# AHD_Ethernet.net
KiCad netlist of a schematic drawn in Altium Designer
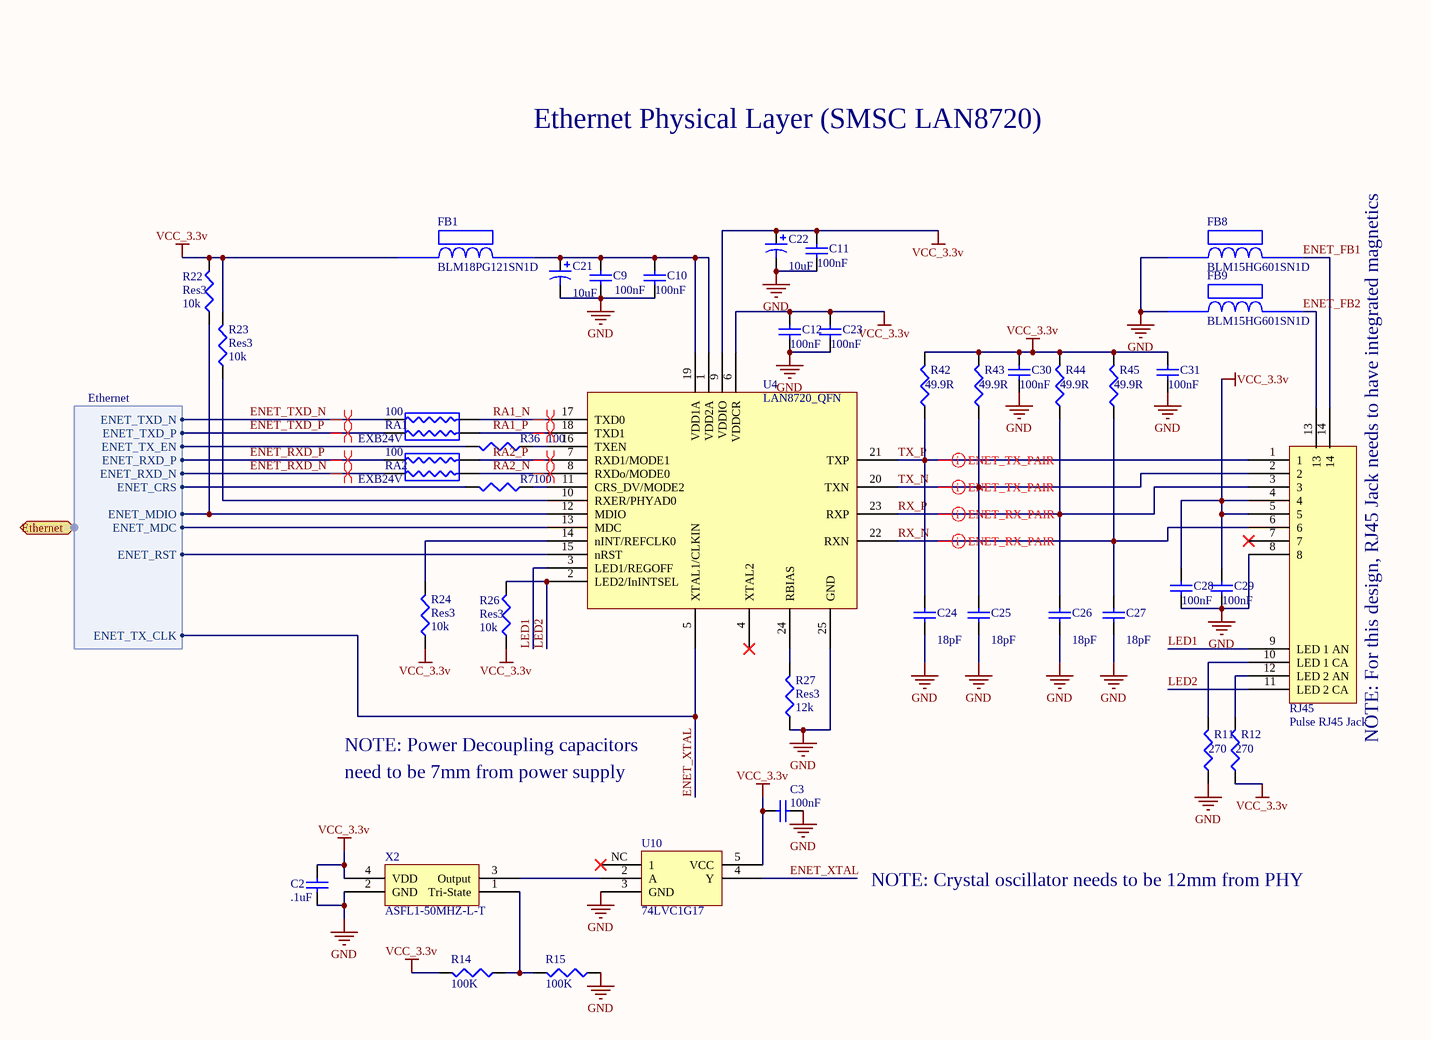
[diagram p0: AHD Ethernet.SchDoc]

(export (version "E")
  (design (tool "Eeschema 10.0.6"))
  (components
    (comp (ref "C2")
      (value ".1uF")
      (footprint "1608[0603]")
      (description "Capacitor (Semiconductor SIM Model)")
      (fields (field (name "Comment") "Cap Semi") (field (name "PUBLISHER") "Altium Limited"))
      (libsource (lib "Miscellaneous Devices") (part "Cap Semi"))
    )
    (comp (ref "C3")
      (value "100nF")
      (footprint "1608[0603]")
      (description "Capacitor (Semiconductor SIM Model)")
      (fields (field (name "Comment") "Cap Semi") (field (name "PUBLISHER") "Altium Limited"))
      (libsource (lib "Miscellaneous Devices") (part "Cap Semi"))
    )
    (comp (ref "C9")
      (value "100nF")
      (footprint "1608[0603]")
      (description "Capacitor (Semiconductor SIM Model)")
      (fields (field (name "Comment") "Cap Semi") (field (name "PUBLISHER") "Altium Limited"))
      (libsource (lib "Miscellaneous Devices") (part "Cap Semi"))
    )
    (comp (ref "C10")
      (value "100nF")
      (footprint "1608[0603]")
      (description "Capacitor (Semiconductor SIM Model)")
      (fields (field (name "Comment") "Cap Semi") (field (name "PUBLISHER") "Altium Limited"))
      (libsource (lib "Miscellaneous Devices") (part "Cap Semi"))
    )
    (comp (ref "C11")
      (value "100nF")
      (footprint "1608[0603]")
      (description "Capacitor (Semiconductor SIM Model)")
      (fields (field (name "Comment") "Cap Semi") (field (name "PUBLISHER") "Altium Limited"))
      (libsource (lib "Miscellaneous Devices") (part "Cap Semi"))
    )
    (comp (ref "C12")
      (value "100nF")
      (footprint "1608[0603]")
      (description "Capacitor (Semiconductor SIM Model)")
      (fields (field (name "Comment") "Cap Semi") (field (name "PUBLISHER") "Altium Limited"))
      (libsource (lib "Miscellaneous Devices") (part "Cap Semi"))
    )
    (comp (ref "C21")
      (value "10uF")
      (footprint "CAPC1608L")
      (description "Polarized Capacitor (Surface Mount)")
      (fields (field (name "Comment") "Cap Pol3") (field (name "PUBLISHER") "Altium Limited"))
      (libsource (lib "Miscellaneous Devices") (part "Cap Pol3"))
    )
    (comp (ref "C22")
      (value "10uF")
      (footprint "CAPC1608L")
      (description "Polarized Capacitor (Surface Mount)")
      (fields (field (name "Comment") "Cap Pol3") (field (name "PUBLISHER") "Altium Limited"))
      (libsource (lib "Miscellaneous Devices") (part "Cap Pol3"))
    )
    (comp (ref "C23")
      (value "100nF")
      (footprint "1608[0603]")
      (description "Capacitor (Semiconductor SIM Model)")
      (fields (field (name "Comment") "Cap Semi") (field (name "PUBLISHER") "Altium Limited"))
      (libsource (lib "Miscellaneous Devices") (part "Cap Semi"))
    )
    (comp (ref "C24")
      (value "18pF")
      (footprint "1608[0603]")
      (description "Capacitor (Semiconductor SIM Model)")
      (fields (field (name "Comment") "Cap Semi") (field (name "PUBLISHER") "Altium Limited"))
      (libsource (lib "Miscellaneous Devices") (part "Cap Semi"))
    )
    (comp (ref "C25")
      (value "18pF")
      (footprint "1608[0603]")
      (description "Capacitor (Semiconductor SIM Model)")
      (fields (field (name "Comment") "Cap Semi") (field (name "PUBLISHER") "Altium Limited"))
      (libsource (lib "Miscellaneous Devices") (part "Cap Semi"))
    )
    (comp (ref "C26")
      (value "18pF")
      (footprint "1608[0603]")
      (description "Capacitor (Semiconductor SIM Model)")
      (fields (field (name "Comment") "Cap Semi") (field (name "PUBLISHER") "Altium Limited"))
      (libsource (lib "Miscellaneous Devices") (part "Cap Semi"))
    )
    (comp (ref "C27")
      (value "18pF")
      (footprint "1608[0603]")
      (description "Capacitor (Semiconductor SIM Model)")
      (fields (field (name "Comment") "Cap Semi") (field (name "PUBLISHER") "Altium Limited"))
      (libsource (lib "Miscellaneous Devices") (part "Cap Semi"))
    )
    (comp (ref "C28")
      (value "100nF")
      (footprint "1608[0603]")
      (description "Capacitor (Semiconductor SIM Model)")
      (fields (field (name "Comment") "Cap Semi") (field (name "PUBLISHER") "Altium Limited"))
      (libsource (lib "Miscellaneous Devices") (part "Cap Semi"))
    )
    (comp (ref "C29")
      (value "100nF")
      (footprint "1608[0603]")
      (description "Capacitor (Semiconductor SIM Model)")
      (fields (field (name "Comment") "Cap Semi") (field (name "PUBLISHER") "Altium Limited"))
      (libsource (lib "Miscellaneous Devices") (part "Cap Semi"))
    )
    (comp (ref "C30")
      (value "100nF")
      (footprint "1608[0603]")
      (description "Capacitor (Semiconductor SIM Model)")
      (fields (field (name "Comment") "Cap Semi") (field (name "PUBLISHER") "Altium Limited"))
      (libsource (lib "Miscellaneous Devices") (part "Cap Semi"))
    )
    (comp (ref "C31")
      (value "100nF")
      (footprint "1608[0603]")
      (description "Capacitor (Semiconductor SIM Model)")
      (fields (field (name "Comment") "Cap Semi") (field (name "PUBLISHER") "Altium Limited"))
      (libsource (lib "Miscellaneous Devices") (part "Cap Semi"))
    )
    (comp (ref "FB1")
      (value "BLM18PG121SN1D")
      (footprint "BLM18PG121SN1D")
      (libsource (lib "AHD Part Library") (part "BLM18PG121SN1D"))
    )
    (comp (ref "FB8")
      (value "BLM15HG601SN1D")
      (footprint "BLM18PG121SN1D")
      (libsource (lib "AHD Part Library") (part "BLM15HG601SN1D"))
    )
    (comp (ref "FB9")
      (value "BLM15HG601SN1D")
      (footprint "BLM18PG121SN1D")
      (libsource (lib "AHD Part Library") (part "BLM15HG601SN1D"))
    )
    (comp (ref "R7")
      (value "100")
      (footprint "J1-0603")
      (description "Resistor")
      (fields (field (name "Comment") "Res3") (field (name "PUBLISHER") "Altium Limited"))
      (libsource (lib "Miscellaneous Devices") (part "Res3"))
    )
    (comp (ref "R11")
      (value "270")
      (footprint "J1-0603")
      (description "Resistor")
      (fields (field (name "Comment") "Res3") (field (name "PUBLISHER") "Altium Limited"))
      (libsource (lib "Miscellaneous Devices") (part "Res3"))
    )
    (comp (ref "R12")
      (value "270")
      (footprint "J1-0603")
      (description "Resistor")
      (fields (field (name "Comment") "Res3") (field (name "PUBLISHER") "Altium Limited"))
      (libsource (lib "Miscellaneous Devices") (part "Res3"))
    )
    (comp (ref "R14")
      (value "100K")
      (footprint "J1-0603")
      (description "Resistor")
      (fields (field (name "Comment") "Res3") (field (name "PUBLISHER") "Altium Limited"))
      (libsource (lib "Miscellaneous Devices") (part "Res3"))
    )
    (comp (ref "R15")
      (value "100K")
      (footprint "J1-0603")
      (description "Resistor")
      (fields (field (name "Comment") "Res3") (field (name "PUBLISHER") "Altium Limited"))
      (libsource (lib "Miscellaneous Devices") (part "Res3"))
    )
    (comp (ref "R22")
      (value "Res3")
      (footprint "J1-0603")
      (description "Resistor")
      (fields (field (name "ALTIUM_VALUE") "10k") (field (name "PUBLISHER") "Altium Limited"))
      (libsource (lib "Miscellaneous Devices") (part "Res3"))
    )
    (comp (ref "R23")
      (value "Res3")
      (footprint "J1-0603")
      (description "Resistor")
      (fields (field (name "ALTIUM_VALUE") "10k") (field (name "PUBLISHER") "Altium Limited"))
      (libsource (lib "Miscellaneous Devices") (part "Res3"))
    )
    (comp (ref "R24")
      (value "Res3")
      (footprint "J1-0603")
      (description "Resistor")
      (fields (field (name "ALTIUM_VALUE") "10k") (field (name "PUBLISHER") "Altium Limited"))
      (libsource (lib "Miscellaneous Devices") (part "Res3"))
    )
    (comp (ref "R26")
      (value "Res3")
      (footprint "J1-0603")
      (description "Resistor")
      (fields (field (name "ALTIUM_VALUE") "10k") (field (name "PUBLISHER") "Altium Limited"))
      (libsource (lib "Miscellaneous Devices") (part "Res3"))
    )
    (comp (ref "R27")
      (value "Res3")
      (footprint "J1-0603")
      (description "Resistor")
      (fields (field (name "ALTIUM_VALUE") "12k") (field (name "PUBLISHER") "Altium Limited"))
      (libsource (lib "Miscellaneous Devices") (part "Res3"))
    )
    (comp (ref "R36")
      (value "100")
      (footprint "J1-0603")
      (description "Resistor")
      (fields (field (name "Comment") "Res3") (field (name "PUBLISHER") "Altium Limited"))
      (libsource (lib "Miscellaneous Devices") (part "Res3"))
    )
    (comp (ref "R42")
      (value "49.9R")
      (footprint "J1-0603")
      (description "Resistor")
      (fields (field (name "Comment") "Res3") (field (name "PUBLISHER") "Altium Limited"))
      (libsource (lib "Miscellaneous Devices") (part "Res3"))
    )
    (comp (ref "R43")
      (value "49.9R")
      (footprint "J1-0603")
      (description "Resistor")
      (fields (field (name "Comment") "Res3") (field (name "PUBLISHER") "Altium Limited"))
      (libsource (lib "Miscellaneous Devices") (part "Res3"))
    )
    (comp (ref "R44")
      (value "49.9R")
      (footprint "J1-0603")
      (description "Resistor")
      (fields (field (name "Comment") "Res3") (field (name "PUBLISHER") "Altium Limited"))
      (libsource (lib "Miscellaneous Devices") (part "Res3"))
    )
    (comp (ref "R45")
      (value "49.9R")
      (footprint "J1-0603")
      (description "Resistor")
      (fields (field (name "Comment") "Res3") (field (name "PUBLISHER") "Altium Limited"))
      (libsource (lib "Miscellaneous Devices") (part "Res3"))
    )
    (comp (ref "RA1")
      (value "EXB24V")
      (footprint "EXB24V - Res Array x2")
      (fields (field (name "ALTIUM_VALUE") "100"))
      (libsource (lib "AHD Part Library") (part "EXB24V - Res Array x2"))
    )
    (comp (ref "RA2")
      (value "EXB24V")
      (footprint "EXB24V - Res Array x2")
      (fields (field (name "ALTIUM_VALUE") "100"))
      (libsource (lib "AHD Part Library") (part "EXB24V - Res Array x2"))
    )
    (comp (ref "RJ45")
      (value "Pulse RJ45 Jack")
      (footprint "J0006D21BNL")
      (libsource (lib "AHD Part Library") (part "Pulse RJ45_ICM_LED_Jack"))
    )
    (comp (ref "U4")
      (value "LAN8720_QFN")
      (footprint "LAN8720_QFN")
      (libsource (lib "AHD Part Library") (part "LAN8720 QFN"))
    )
    (comp (ref "U10")
      (value "74LVC1G17")
      (footprint "74LVC1G17")
      (libsource (lib "AHD Part Library") (part "74LVC1G17"))
    )
    (comp (ref "X2")
      (value "ASFL1-50MHZ-L-T")
      (footprint "ASFL1-50MHZ-L-T")
      (libsource (lib "AHD Part Library") (part "ASFL1-50MHZ-L-T"))
    )
  )
  (nets
    (net (code "2") (name "/ENET_CRS") (class "Default")
      (node (ref "R7") (pin "2") (pinfunction "2_2") (pintype "passive"))
    )
    (net (code "3") (name "/ENET_FB1") (class "Default")
      (node (ref "FB8") (pin "2") (pinfunction "2_2") (pintype "passive"))
      (node (ref "RJ45") (pin "14") (pinfunction "14_14") (pintype "passive"))
    )
    (net (code "4") (name "/ENET_FB2") (class "Default")
      (node (ref "FB9") (pin "2") (pinfunction "2_2") (pintype "passive"))
      (node (ref "RJ45") (pin "13") (pinfunction "13_13") (pintype "passive"))
    )
    (net (code "5") (name "/ENET_MDC") (class "Default")
      (node (ref "U4") (pin "13") (pinfunction "MDC_13") (pintype "passive"))
    )
    (net (code "6") (name "/ENET_MDIO") (class "Default")
      (node (ref "R22") (pin "1") (pinfunction "1_1") (pintype "passive"))
      (node (ref "U4") (pin "12") (pinfunction "MDIO_12") (pintype "passive"))
    )
    (net (code "7") (name "/ENET_RST") (class "Default")
      (node (ref "U4") (pin "15") (pinfunction "nRST_15") (pintype "passive"))
    )
    (net (code "8") (name "/ENET_RXD_N") (class "Default")
      (node (ref "RA2") (pin "1") (pinfunction "1_1") (pintype "passive"))
    )
    (net (code "9") (name "/ENET_RXD_P") (class "Default")
      (node (ref "RA2") (pin "3") (pinfunction "3_3") (pintype "passive"))
    )
    (net (code "10") (name "/ENET_TXD_N") (class "Default")
      (node (ref "RA1") (pin "3") (pinfunction "3_3") (pintype "passive"))
    )
    (net (code "11") (name "/ENET_TXD_P") (class "Default")
      (node (ref "RA1") (pin "1") (pinfunction "1_1") (pintype "passive"))
    )
    (net (code "12") (name "/ENET_TX_EN") (class "Default")
      (node (ref "R36") (pin "2") (pinfunction "2_2") (pintype "passive"))
    )
    (net (code "13") (name "/ENET_XTAL") (class "Default")
      (node (ref "U10") (pin "4") (pinfunction "Y_4") (pintype "passive"))
      (node (ref "U4") (pin "5") (pinfunction "XTAL1/CLKIN_5") (pintype "passive"))
    )
    (net (code "14") (name "/LED1") (class "Default")
      (node (ref "RJ45") (pin "9") (pinfunction "LED_1_AN_9") (pintype "passive"))
      (node (ref "U4") (pin "3") (pinfunction "LED1/REGOFF_3") (pintype "passive"))
    )
    (net (code "15") (name "/LED2") (class "Default")
      (node (ref "R26") (pin "2") (pinfunction "2_2") (pintype "passive"))
      (node (ref "RJ45") (pin "11") (pinfunction "LED_2_CA_11") (pintype "passive"))
      (node (ref "U4") (pin "2") (pinfunction "LED2/InINTSEL_2") (pintype "passive"))
    )
    (net (code "16") (name "/RA1_N") (class "Default")
      (node (ref "RA1") (pin "4") (pinfunction "4_4") (pintype "passive"))
      (node (ref "U4") (pin "17") (pinfunction "TXD0_17") (pintype "passive"))
    )
    (net (code "17") (name "/RA1_P") (class "Default")
      (node (ref "RA1") (pin "2") (pinfunction "2_2") (pintype "passive"))
      (node (ref "U4") (pin "18") (pinfunction "TXD1_18") (pintype "passive"))
    )
    (net (code "18") (name "/RA2_N") (class "Default")
      (node (ref "RA2") (pin "2") (pinfunction "2_2") (pintype "passive"))
      (node (ref "U4") (pin "8") (pinfunction "RXDo/MODE0_8") (pintype "passive"))
    )
    (net (code "19") (name "/RA2_P") (class "Default")
      (node (ref "RA2") (pin "4") (pinfunction "4_4") (pintype "passive"))
      (node (ref "U4") (pin "7") (pinfunction "RXD1/MODE1_7") (pintype "passive"))
    )
    (net (code "20") (name "/RX_N") (class "Default")
      (node (ref "C27") (pin "2") (pinfunction "2_2") (pintype "passive"))
      (node (ref "R45") (pin "1") (pinfunction "1_1") (pintype "passive"))
      (node (ref "RJ45") (pin "6") (pinfunction "6_6") (pintype "passive"))
      (node (ref "U4") (pin "22") (pinfunction "RXN_22") (pintype "passive"))
    )
    (net (code "21") (name "/RX_P") (class "Default")
      (node (ref "C26") (pin "2") (pinfunction "2_2") (pintype "passive"))
      (node (ref "R44") (pin "1") (pinfunction "1_1") (pintype "passive"))
      (node (ref "RJ45") (pin "3") (pinfunction "3_3") (pintype "passive"))
      (node (ref "U4") (pin "23") (pinfunction "RXP_23") (pintype "passive"))
    )
    (net (code "22") (name "/TX_N") (class "Default")
      (node (ref "C25") (pin "2") (pinfunction "2_2") (pintype "passive"))
      (node (ref "R43") (pin "1") (pinfunction "1_1") (pintype "passive"))
      (node (ref "RJ45") (pin "2") (pinfunction "2_2") (pintype "passive"))
      (node (ref "U4") (pin "20") (pinfunction "TXN_20") (pintype "passive"))
    )
    (net (code "23") (name "/TX_P") (class "Default")
      (node (ref "C24") (pin "2") (pinfunction "2_2") (pintype "passive"))
      (node (ref "R42") (pin "1") (pinfunction "1_1") (pintype "passive"))
      (node (ref "RJ45") (pin "1") (pinfunction "1_1") (pintype "passive"))
      (node (ref "U4") (pin "21") (pinfunction "TXP_21") (pintype "passive"))
    )
    (net (code "25") (name "GND") (class "Default")
      (node (ref "C10") (pin "1") (pinfunction "1_1") (pintype "passive"))
      (node (ref "C11") (pin "1") (pinfunction "1_1") (pintype "passive"))
      (node (ref "C12") (pin "1") (pinfunction "1_1") (pintype "passive"))
      (node (ref "C2") (pin "1") (pinfunction "1_1") (pintype "passive"))
      (node (ref "C21") (pin "2") (pinfunction "2_2") (pintype "passive"))
      (node (ref "C22") (pin "2") (pinfunction "2_2") (pintype "passive"))
      (node (ref "C23") (pin "1") (pinfunction "1_1") (pintype "passive"))
      (node (ref "C24") (pin "1") (pinfunction "1_1") (pintype "passive"))
      (node (ref "C25") (pin "1") (pinfunction "1_1") (pintype "passive"))
      (node (ref "C26") (pin "1") (pinfunction "1_1") (pintype "passive"))
      (node (ref "C27") (pin "1") (pinfunction "1_1") (pintype "passive"))
      (node (ref "C28") (pin "1") (pinfunction "1_1") (pintype "passive"))
      (node (ref "C29") (pin "1") (pinfunction "1_1") (pintype "passive"))
      (node (ref "C3") (pin "1") (pinfunction "1_1") (pintype "passive"))
      (node (ref "C30") (pin "1") (pinfunction "1_1") (pintype "passive"))
      (node (ref "C31") (pin "1") (pinfunction "1_1") (pintype "passive"))
      (node (ref "C9") (pin "1") (pinfunction "1_1") (pintype "passive"))
      (node (ref "FB8") (pin "1") (pinfunction "1_1") (pintype "passive"))
      (node (ref "FB9") (pin "1") (pinfunction "1_1") (pintype "passive"))
      (node (ref "R11") (pin "1") (pinfunction "1_1") (pintype "passive"))
      (node (ref "R15") (pin "1") (pinfunction "1_1") (pintype "passive"))
      (node (ref "R27") (pin "1") (pinfunction "1_1") (pintype "passive"))
      (node (ref "RJ45") (pin "8") (pinfunction "8_8") (pintype "passive"))
      (node (ref "U10") (pin "3") (pinfunction "GND_3") (pintype "passive"))
      (node (ref "U4") (pin "25") (pinfunction "GND_25") (pintype "passive"))
      (node (ref "X2") (pin "2") (pinfunction "GND_2") (pintype "passive"))
    )
    (net (code "26") (name "Net-(RJ45-LED_1_CA)") (class "Default")
      (node (ref "R11") (pin "2") (pinfunction "2_2") (pintype "passive"))
      (node (ref "RJ45") (pin "10") (pinfunction "LED_1_CA_10") (pintype "passive"))
    )
    (net (code "27") (name "Net-(RJ45-LED_2_AN)") (class "Default")
      (node (ref "R12") (pin "2") (pinfunction "2_2") (pintype "passive"))
      (node (ref "RJ45") (pin "12") (pinfunction "LED_2_AN_12") (pintype "passive"))
    )
    (net (code "28") (name "Net-(U4-CRS_DV{slash}MODE2)") (class "Default")
      (node (ref "R7") (pin "1") (pinfunction "1_1") (pintype "passive"))
      (node (ref "U4") (pin "11") (pinfunction "CRS_DV/MODE2_11") (pintype "passive"))
    )
    (net (code "29") (name "Net-(U4-RBIAS)") (class "Default")
      (node (ref "R27") (pin "2") (pinfunction "2_2") (pintype "passive"))
      (node (ref "U4") (pin "24") (pinfunction "RBIAS_24") (pintype "passive"))
    )
    (net (code "30") (name "Net-(U4-RXER{slash}PHYAD0)") (class "Default")
      (node (ref "R23") (pin "1") (pinfunction "1_1") (pintype "passive"))
      (node (ref "U4") (pin "10") (pinfunction "RXER/PHYAD0_10") (pintype "passive"))
    )
    (net (code "31") (name "Net-(U4-TXEN)") (class "Default")
      (node (ref "R36") (pin "1") (pinfunction "1_1") (pintype "passive"))
      (node (ref "U4") (pin "16") (pinfunction "TXEN_16") (pintype "passive"))
    )
    (net (code "32") (name "Net-(U4-VDD1A)") (class "Default")
      (node (ref "C10") (pin "2") (pinfunction "2_2") (pintype "passive"))
      (node (ref "C21") (pin "1") (pinfunction "1_1") (pintype "passive"))
      (node (ref "C9") (pin "2") (pinfunction "2_2") (pintype "passive"))
      (node (ref "FB1") (pin "2") (pinfunction "2_2") (pintype "passive"))
      (node (ref "U4") (pin "1") (pinfunction "VDD2A_1") (pintype "passive"))
      (node (ref "U4") (pin "19") (pinfunction "VDD1A_19") (pintype "passive"))
    )
    (net (code "33") (name "Net-(U4-nINT{slash}REFCLK0)") (class "Default")
      (node (ref "R24") (pin "2") (pinfunction "2_2") (pintype "passive"))
      (node (ref "U4") (pin "14") (pinfunction "nINT/REFCLK0_14") (pintype "passive"))
    )
    (net (code "34") (name "Net-(U10-A)") (class "Default")
      (node (ref "U10") (pin "2") (pinfunction "A_2") (pintype "passive"))
      (node (ref "X2") (pin "3") (pinfunction "Output_3") (pintype "passive"))
    )
    (net (code "35") (name "Net-(X2-Tri-State)") (class "Default")
      (node (ref "R14") (pin "1") (pinfunction "1_1") (pintype "passive"))
      (node (ref "R15") (pin "2") (pinfunction "2_2") (pintype "passive"))
      (node (ref "X2") (pin "1") (pinfunction "Tri-State_1") (pintype "passive"))
    )
    (net (code "36") (name "VCC_3.3v") (class "Default")
      (node (ref "C11") (pin "2") (pinfunction "2_2") (pintype "passive"))
      (node (ref "C12") (pin "2") (pinfunction "2_2") (pintype "passive"))
      (node (ref "C2") (pin "2") (pinfunction "2_2") (pintype "passive"))
      (node (ref "C22") (pin "1") (pinfunction "1_1") (pintype "passive"))
      (node (ref "C23") (pin "2") (pinfunction "2_2") (pintype "passive"))
      (node (ref "C28") (pin "2") (pinfunction "2_2") (pintype "passive"))
      (node (ref "C29") (pin "2") (pinfunction "2_2") (pintype "passive"))
      (node (ref "C3") (pin "2") (pinfunction "2_2") (pintype "passive"))
      (node (ref "C30") (pin "2") (pinfunction "2_2") (pintype "passive"))
      (node (ref "C31") (pin "2") (pinfunction "2_2") (pintype "passive"))
      (node (ref "FB1") (pin "1") (pinfunction "1_1") (pintype "passive"))
      (node (ref "R12") (pin "1") (pinfunction "1_1") (pintype "passive"))
      (node (ref "R14") (pin "2") (pinfunction "2_2") (pintype "passive"))
      (node (ref "R22") (pin "2") (pinfunction "2_2") (pintype "passive"))
      (node (ref "R23") (pin "2") (pinfunction "2_2") (pintype "passive"))
      (node (ref "R24") (pin "1") (pinfunction "1_1") (pintype "passive"))
      (node (ref "R26") (pin "1") (pinfunction "1_1") (pintype "passive"))
      (node (ref "R42") (pin "2") (pinfunction "2_2") (pintype "passive"))
      (node (ref "R43") (pin "2") (pinfunction "2_2") (pintype "passive"))
      (node (ref "R44") (pin "2") (pinfunction "2_2") (pintype "passive"))
      (node (ref "R45") (pin "2") (pinfunction "2_2") (pintype "passive"))
      (node (ref "RJ45") (pin "4") (pinfunction "4_4") (pintype "passive"))
      (node (ref "RJ45") (pin "5") (pinfunction "5_5") (pintype "passive"))
      (node (ref "U10") (pin "5") (pinfunction "VCC_5") (pintype "passive"))
      (node (ref "U4") (pin "6") (pinfunction "VDDCR_6") (pintype "passive"))
      (node (ref "U4") (pin "9") (pinfunction "VDDIO_9") (pintype "passive"))
      (node (ref "X2") (pin "4") (pinfunction "VDD_4") (pintype "passive"))
    )
    (net (code "37") (name "unconnected-(RJ45-Pad7)") (class "Default")
      (node (ref "RJ45") (pin "7") (pinfunction "7_7") (pintype "passive+no_connect"))
    )
    (net (code "38") (name "unconnected-(U4-XTAL2-Pad4)") (class "Default")
      (node (ref "U4") (pin "4") (pinfunction "XTAL2_4") (pintype "passive+no_connect"))
    )
    (net (code "39") (name "unconnected-(U10-1-PadNC)") (class "Default")
      (node (ref "U10") (pin "NC") (pinfunction "1_NC") (pintype "passive+no_connect"))
    )
  )
)
